# debugging_board_3_MCU.net
KiCad netlist of a schematic drawn in Altium Designer
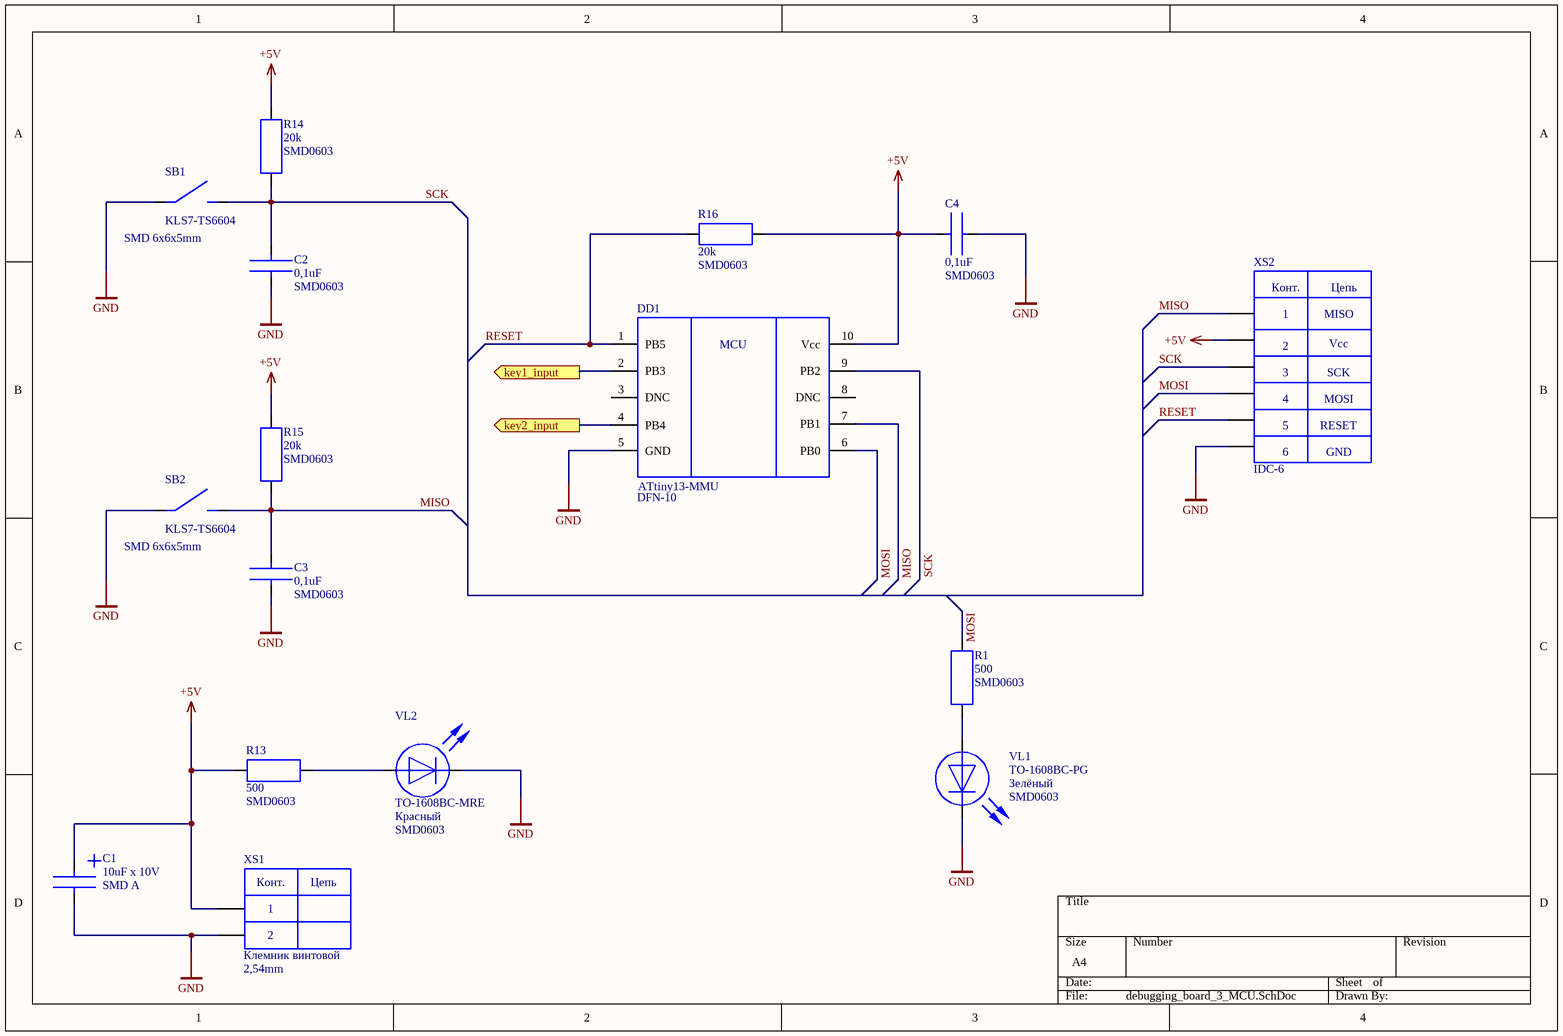
[diagram p0: debugging_board_3_MCU.SchDoc]

(export (version "E")
  (design (tool "Eeschema 10.0.6"))
  (components
    (comp (ref "C1")
      (value "10uF x 10V")
      (footprint "TANT_CAP_A(3216)")
      (fields (field (name "PACKAGE") "SMD A"))
      (libsource (lib "MechanikLibrary") (part "C_TANT_A"))
    )
    (comp (ref "C2")
      (value "0,1uF")
      (footprint "SMD0603(1005)")
      (fields (field (name "PACKAGE") "SMD0603"))
      (libsource (lib "MechanikLibrary") (part "CER_CUP_0603"))
    )
    (comp (ref "C3")
      (value "0,1uF")
      (footprint "SMD0603(1005)")
      (fields (field (name "PACKAGE") "SMD0603"))
      (libsource (lib "MechanikLibrary") (part "CER_CUP_0603"))
    )
    (comp (ref "C4")
      (value "0,1uF")
      (footprint "SMD0603(1005)")
      (fields (field (name "PACKAGE") "SMD0603"))
      (libsource (lib "MechanikLibrary") (part "CER_CUP_0603"))
    )
    (comp (ref "DD1")
      (value "ATtiny13-MMU")
      (footprint "QFN-10")
      (fields (field (name "PACKAGE") "DFN-10"))
      (libsource (lib "MechanikLibrary") (part "ATtiny13-MMU"))
    )
    (comp (ref "R1")
      (value "500")
      (footprint "SMD0603(1005)")
      (fields (field (name "PACKAGE") "SMD0603"))
      (libsource (lib "MechanikLibrary") (part "R_0603"))
    )
    (comp (ref "R13")
      (value "500")
      (footprint "SMD0603(1005)")
      (fields (field (name "PACKAGE") "SMD0603"))
      (libsource (lib "MechanikLibrary") (part "R_0603"))
    )
    (comp (ref "R14")
      (value "20k")
      (footprint "SMD0603(1005)")
      (fields (field (name "PACKAGE") "SMD0603"))
      (libsource (lib "MechanikLibrary") (part "R_0603"))
    )
    (comp (ref "R15")
      (value "20k")
      (footprint "SMD0603(1005)")
      (fields (field (name "PACKAGE") "SMD0603"))
      (libsource (lib "MechanikLibrary") (part "R_0603"))
    )
    (comp (ref "R16")
      (value "20k")
      (footprint "SMD0603(1005)")
      (fields (field (name "PACKAGE") "SMD0603"))
      (libsource (lib "MechanikLibrary") (part "R_0603"))
    )
    (comp (ref "SB1")
      (value "KLS7-TS6604")
      (footprint "KLS7-TS6604 (IT-1102SA)")
      (fields (field (name "PACKAGE") "SMD 6х6х5mm"))
      (libsource (lib "MechanikLibrary") (part "Кнопка KLS7-TS6604 (IT-1102SA)"))
    )
    (comp (ref "SB2")
      (value "KLS7-TS6604")
      (footprint "KLS7-TS6604 (IT-1102SA)")
      (fields (field (name "PACKAGE") "SMD 6х6х5mm"))
      (libsource (lib "MechanikLibrary") (part "Кнопка KLS7-TS6604 (IT-1102SA)"))
    )
    (comp (ref "VL1")
      (value "TO-1608BC-PG")
      (footprint "LED_SMD0603(1005)")
      (fields (field (name "LIGHT") "Зелёный") (field (name "PACKAGE") "SMD0603"))
      (libsource (lib "MechanikLibrary") (part "LED_0603"))
    )
    (comp (ref "VL2")
      (value "TO-1608BC-MRE")
      (footprint "LED_SMD0603(1005)")
      (fields (field (name "LIGHT") "Красный") (field (name "PACKAGE") "SMD0603"))
      (libsource (lib "MechanikLibrary") (part "LED_0603"))
    )
    (comp (ref "XS1")
      (value "Клемник винтовой")
      (footprint "XS_2x2.54MM")
      (fields (field (name "PACKAGE") "2,54mm"))
      (libsource (lib "MechanikLibrary") (part "Клемник винтовой 2-контактный, 2,54мм"))
    )
    (comp (ref "XS2")
      (value "IDC-6")
      (footprint "IDC-6 (2.54)")
      (libsource (lib "MechanikLibrary") (part "ISP_connector"))
    )
  )
  (nets
    (net (code "1") (name "+5V") (class "Default")
      (node (ref "C1") (pin "1") (pintype "passive"))
      (node (ref "C4") (pin "1") (pintype "passive"))
      (node (ref "DD1") (pin "10") (pinfunction "Vcc_10") (pintype "passive"))
      (node (ref "R13") (pin "1") (pintype "passive"))
      (node (ref "R14") (pin "2") (pintype "passive"))
      (node (ref "R15") (pin "2") (pintype "passive"))
      (node (ref "R16") (pin "2") (pintype "passive"))
      (node (ref "XS1") (pin "1") (pintype "passive"))
      (node (ref "XS2") (pin "2") (pinfunction "DM-_2") (pintype "passive"))
    )
    (net (code "2") (name "/MISO") (class "Default")
      (node (ref "C3") (pin "2") (pintype "passive"))
      (node (ref "DD1") (pin "7") (pinfunction "PB1_7") (pintype "passive"))
      (node (ref "R15") (pin "1") (pintype "passive"))
      (node (ref "SB2") (pin "2") (pintype "passive"))
      (node (ref "XS2") (pin "1") (pinfunction "+5_1") (pintype "passive"))
    )
    (net (code "3") (name "/MOSI") (class "Default")
      (node (ref "DD1") (pin "6") (pinfunction "PB0_6") (pintype "passive"))
      (node (ref "R1") (pin "2") (pintype "passive"))
      (node (ref "XS2") (pin "4") (pinfunction "DM+_4") (pintype "passive"))
    )
    (net (code "4") (name "/RESET") (class "Default")
      (node (ref "DD1") (pin "1") (pinfunction "PB5_1") (pintype "passive"))
      (node (ref "R16") (pin "1") (pintype "passive"))
      (node (ref "XS2") (pin "5") (pinfunction "DM+_5") (pintype "passive"))
    )
    (net (code "5") (name "/SCK") (class "Default")
      (node (ref "C2") (pin "2") (pintype "passive"))
      (node (ref "DD1") (pin "9") (pinfunction "PB2_9") (pintype "passive"))
      (node (ref "R14") (pin "1") (pintype "passive"))
      (node (ref "SB1") (pin "2") (pintype "passive"))
      (node (ref "XS2") (pin "3") (pinfunction "DM+_3") (pintype "passive"))
    )
    (net (code "6") (name "/key1_input") (class "Default")
      (node (ref "DD1") (pin "2") (pinfunction "PB3_2") (pintype "passive"))
    )
    (net (code "7") (name "/key2_input") (class "Default")
      (node (ref "DD1") (pin "4") (pinfunction "PB4_4") (pintype "passive"))
    )
    (net (code "8") (name "GND") (class "Default")
      (node (ref "C1") (pin "2") (pintype "passive"))
      (node (ref "C2") (pin "1") (pintype "passive"))
      (node (ref "C3") (pin "1") (pintype "passive"))
      (node (ref "C4") (pin "2") (pintype "passive"))
      (node (ref "DD1") (pin "5") (pinfunction "GND_5") (pintype "passive"))
      (node (ref "SB1") (pin "1") (pintype "passive"))
      (node (ref "SB2") (pin "1") (pintype "passive"))
      (node (ref "VL1") (pin "2") (pintype "passive"))
      (node (ref "VL2") (pin "2") (pintype "passive"))
      (node (ref "XS1") (pin "2") (pintype "passive"))
      (node (ref "XS2") (pin "6") (pinfunction "DM+_6") (pintype "passive"))
    )
    (net (code "9") (name "Net-(R1-Pad1)") (class "Default")
      (node (ref "R1") (pin "1") (pintype "passive"))
      (node (ref "VL1") (pin "1") (pintype "passive"))
    )
    (net (code "10") (name "Net-(R13-Pad2)") (class "Default")
      (node (ref "R13") (pin "2") (pintype "passive"))
      (node (ref "VL2") (pin "1") (pintype "passive"))
    )
    (net (code "11") (name "unconnected-(DD1-DNC-Pad3)") (class "Default")
      (node (ref "DD1") (pin "3") (pinfunction "DNC_3") (pintype "passive"))
    )
    (net (code "12") (name "unconnected-(DD1-DNC-Pad8)") (class "Default")
      (node (ref "DD1") (pin "8") (pinfunction "DNC_8") (pintype "passive"))
    )
  )
)
